# Mainboard_Power_Interface.net
KiCad netlist of a schematic drawn in Altium Designer
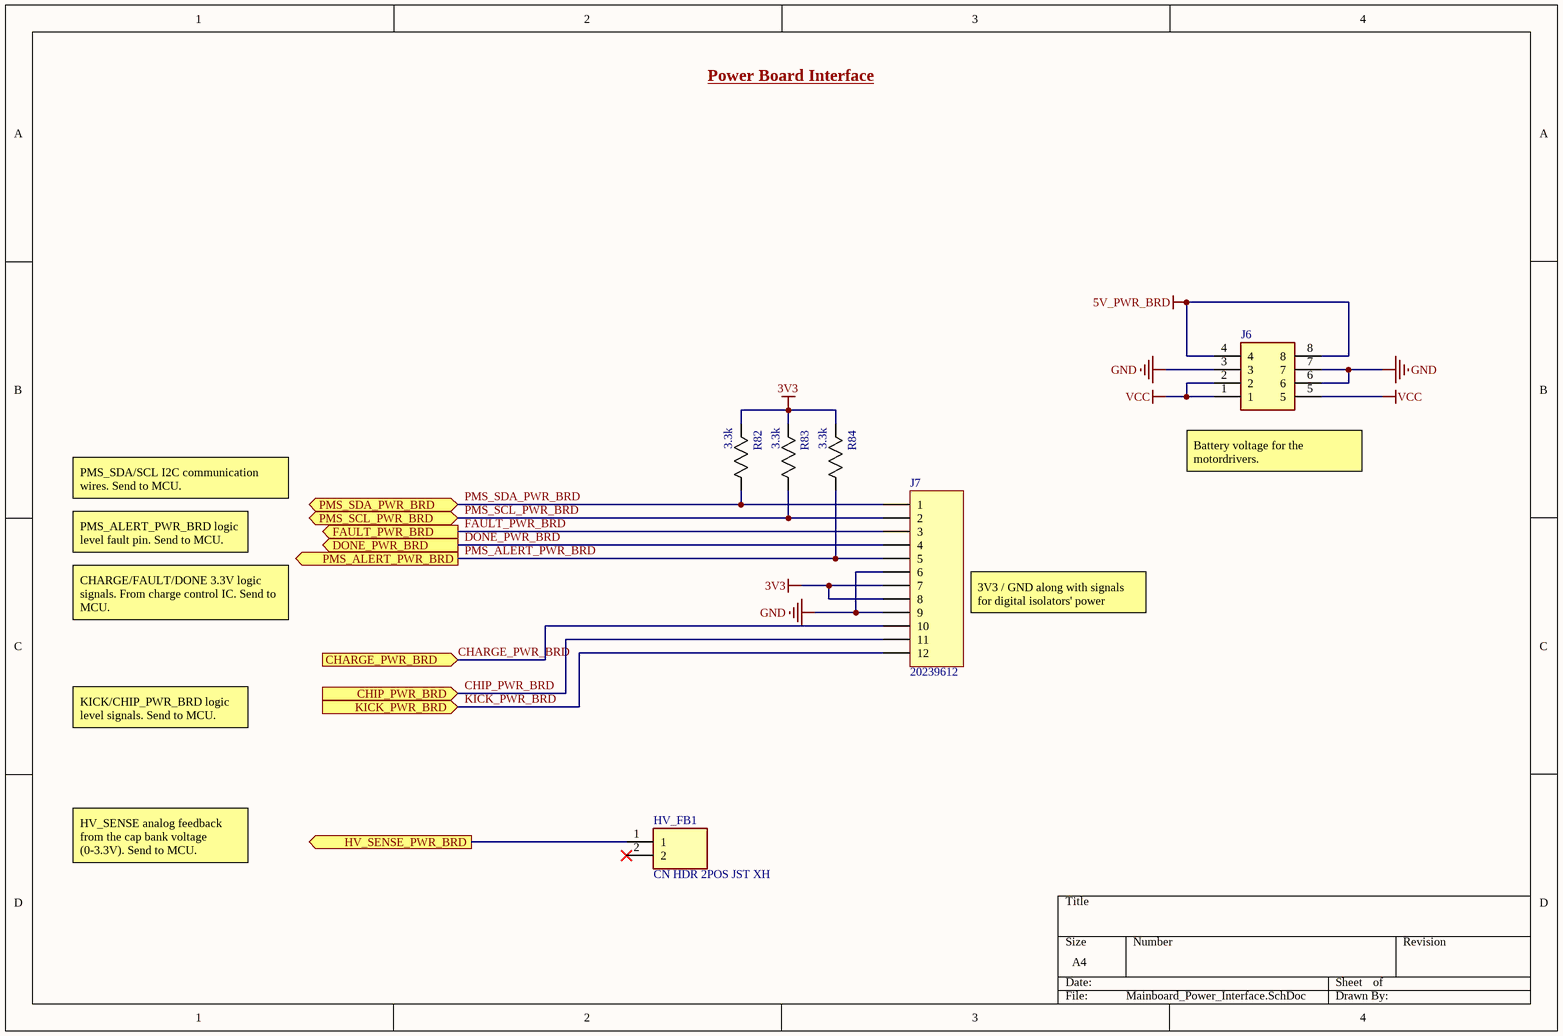
[diagram p0: Mainboard_Power_Interface.SchDoc]

(export (version "E")
  (design (tool "Eeschema 10.0.6"))
  (components
    (comp (ref "HV_FB1")
      (value "CN HDR 2POS JST XH")
      (footprint "JST_B2B-XH-A(LF)(SN)")
      (description "Connector Header Through Hole 2 position 0.098 _2.50mm_\r\nJST XH")
      (fields (field (name "MP") "B2B-XH-A_LF__SN_") (field (name "MF") "JST Sales"))
      (libsource (lib "AltiumLibraries") (part "CN HDR 2POS JST XH"))
    )
    (comp (ref "J6")
      (value "CN HDR 8POS Molex 43045-0812 (R)")
      (footprint "4304508")
      (description "Molex 43045-0812 8POS Microfit\r\nDR TH Vertical")
      (libsource (lib "AltiumLibraries") (part "CN HDR 8POS Molex 43045-0812 (R)"))
    )
    (comp (ref "J7")
      (value "20239612")
      (footprint "CN 20355612")
      (description "12 POS Right Angle Pico Clasp Surface Mount")
      (libsource (lib "AltiumLibraries") (part "CN Pico Clasp 12POS"))
    )
    (comp (ref "R82")
      (value "3.3k")
      (footprint "0603")
      (description "RES SMD 3.3K OHM 5% 1/8W 0805")
      (fields (field (name "TOLERANCE") "5%"))
      (libsource (lib "") (part "RES 3.3k 1/8W_1"))
    )
    (comp (ref "R83")
      (value "3.3k")
      (footprint "0603")
      (description "RES SMD 3.3K OHM 5% 1/8W 0805")
      (fields (field (name "TOLERANCE") "5%"))
      (libsource (lib "AltiumLibraries") (part "RES 3.3k 1/8W"))
    )
    (comp (ref "R84")
      (value "3.3k")
      (footprint "0603")
      (description "RES SMD 3.3K OHM 5% 1/8W 0805")
      (fields (field (name "TOLERANCE") "5%"))
      (libsource (lib "AltiumLibraries") (part "RES 3.3k 1/8W"))
    )
  )
  (nets
    (net (code "1") (name "/CHARGE_PWR_BRD") (class "Default")
      (node (ref "J7") (pin "10") (pinfunction "10_10") (pintype "passive"))
    )
    (net (code "2") (name "/CHIP_PWR_BRD") (class "Default")
      (node (ref "J7") (pin "11") (pinfunction "11_11") (pintype "passive"))
    )
    (net (code "3") (name "/DONE_PWR_BRD") (class "Default")
      (node (ref "J7") (pin "4") (pinfunction "4_4") (pintype "passive"))
    )
    (net (code "4") (name "/FAULT_PWR_BRD") (class "Default")
      (node (ref "J7") (pin "3") (pinfunction "3_3") (pintype "passive"))
    )
    (net (code "5") (name "/HV_SENSE_PWR_BRD") (class "Default")
      (node (ref "HV_FB1") (pin "1") (pinfunction "1_1") (pintype "passive"))
    )
    (net (code "6") (name "/KICK_PWR_BRD") (class "Default")
      (node (ref "J7") (pin "12") (pinfunction "12_12") (pintype "passive"))
    )
    (net (code "7") (name "/PMS_ALERT_PWR_BRD") (class "Default")
      (node (ref "J7") (pin "5") (pinfunction "5_5") (pintype "passive"))
      (node (ref "R84") (pin "1") (pinfunction "R1_1") (pintype "passive"))
    )
    (net (code "8") (name "/PMS_SCL_PWR_BRD") (class "Default")
      (node (ref "J7") (pin "2") (pinfunction "2_2") (pintype "passive"))
      (node (ref "R83") (pin "1") (pinfunction "R1_1") (pintype "passive"))
    )
    (net (code "9") (name "/PMS_SDA_PWR_BRD") (class "Default")
      (node (ref "J7") (pin "1") (pinfunction "1_1") (pintype "passive"))
      (node (ref "R82") (pin "1") (pinfunction "R1_1") (pintype "passive"))
    )
    (net (code "10") (name "3V3") (class "Default")
      (node (ref "J7") (pin "7") (pinfunction "7_7") (pintype "passive"))
      (node (ref "J7") (pin "8") (pinfunction "8_8") (pintype "passive"))
      (node (ref "R82") (pin "2") (pinfunction "R2_2") (pintype "passive"))
      (node (ref "R83") (pin "2") (pinfunction "R2_2") (pintype "passive"))
      (node (ref "R84") (pin "2") (pinfunction "R2_2") (pintype "passive"))
    )
    (net (code "11") (name "5V_PWR_BRD") (class "Default")
      (node (ref "J6") (pin "4") (pinfunction "4_4") (pintype "passive"))
      (node (ref "J6") (pin "8") (pinfunction "8_8") (pintype "passive"))
    )
    (net (code "12") (name "GND") (class "Default")
      (node (ref "J6") (pin "3") (pinfunction "3_3") (pintype "passive"))
      (node (ref "J6") (pin "6") (pinfunction "6_6") (pintype "passive"))
      (node (ref "J6") (pin "7") (pinfunction "7_7") (pintype "passive"))
      (node (ref "J7") (pin "6") (pinfunction "6_6") (pintype "passive"))
      (node (ref "J7") (pin "9") (pinfunction "9_9") (pintype "passive"))
    )
    (net (code "13") (name "VCC") (class "Default")
      (node (ref "J6") (pin "1") (pinfunction "1_1") (pintype "passive"))
      (node (ref "J6") (pin "2") (pinfunction "2_2") (pintype "passive"))
      (node (ref "J6") (pin "5") (pinfunction "5_5") (pintype "passive"))
    )
    (net (code "14") (name "unconnected-(HV_FB1-Pad2)") (class "Default")
      (node (ref "HV_FB1") (pin "2") (pinfunction "2_2") (pintype "passive+no_connect"))
    )
  )
)
